# 5x_SFH_Hoeller_ES.net
KiCad netlist of a schematic drawn in EAGLE
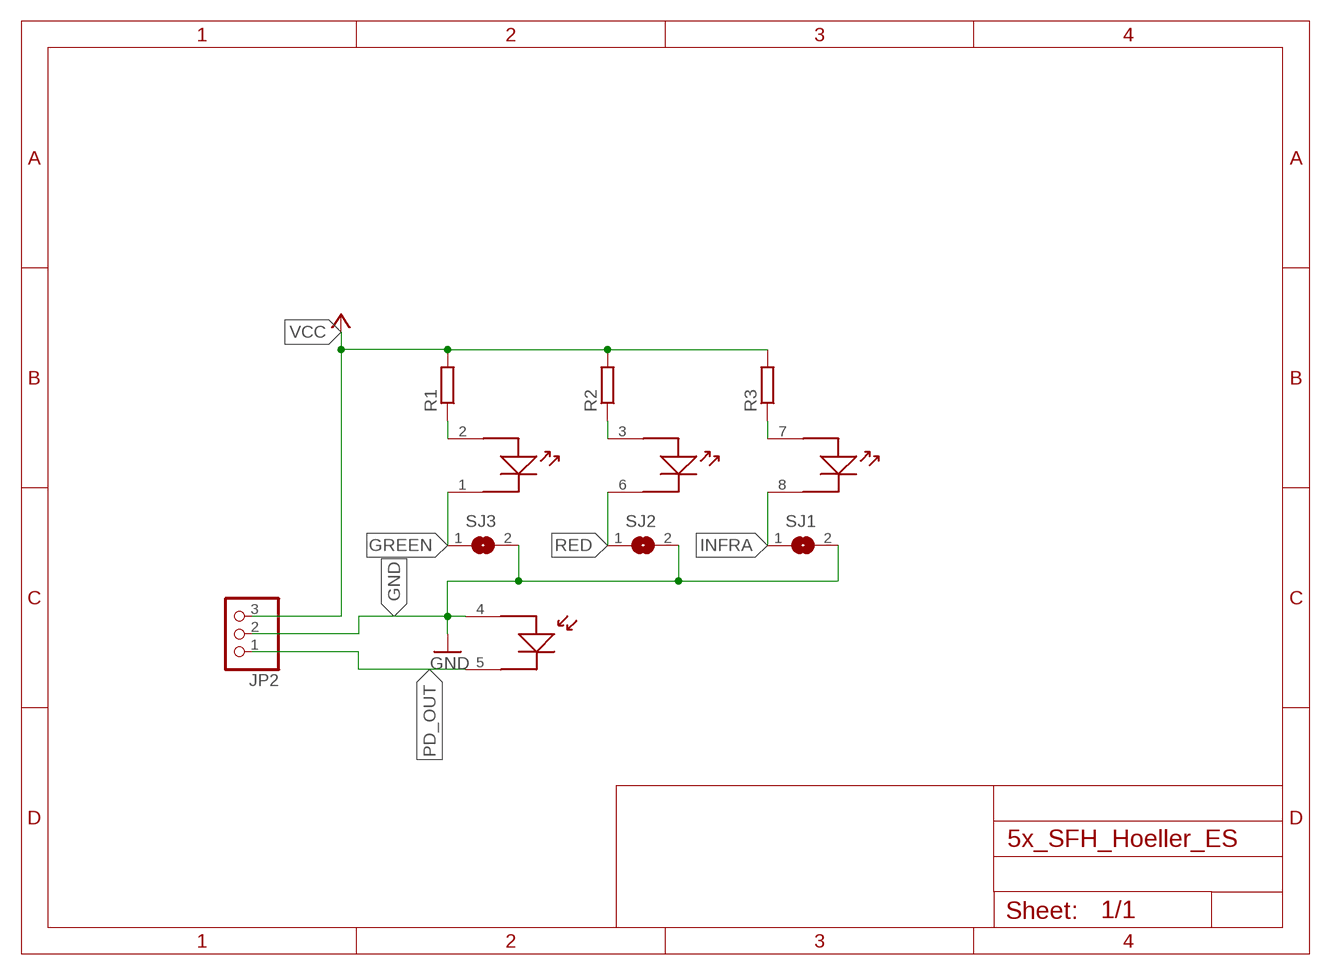
[diagram p0: schematic, sheet 1]

(export (version "E")
  (design (tool "Eeschema 10.0.6"))
  (components
    (comp (ref "JP2")
      (value "PINHD-1X3")
      (footprint "eagle-import:1X03")
      (libsource (lib "eagle-import") (part "PINHD-1X3"))
    )
    (comp (ref "PD-")
      (value "SFH7050_SFH7050")
      (footprint "eagle-import:SFH7050_SFH7050")
      (libsource (lib "eagle-import") (part "SFH7050_SFH7050"))
    )
    (comp (ref "R1")
      (value "R-EU_R0603")
      (footprint "eagle-import:R0603")
      (libsource (lib "eagle-import") (part "R-EU_R0603"))
    )
    (comp (ref "R2")
      (value "R-EU_R0603")
      (footprint "eagle-import:R0603")
      (libsource (lib "eagle-import") (part "R-EU_R0603"))
    )
    (comp (ref "R3")
      (value "R-EU_R0603")
      (footprint "eagle-import:R0603")
      (libsource (lib "eagle-import") (part "R-EU_R0603"))
    )
    (comp (ref "SJ1") (value "SJ") (footprint "eagle-import:SJ") (libsource (lib "eagle-import") (part "SJ")))
    (comp (ref "SJ2") (value "SJ") (footprint "eagle-import:SJ") (libsource (lib "eagle-import") (part "SJ")))
    (comp (ref "SJ3") (value "SJ") (footprint "eagle-import:SJ") (libsource (lib "eagle-import") (part "SJ")))
  )
  (nets
    (net (code "1") (name "GND") (class "Default")
      (node (ref "JP2") (pin "2") (pinfunction "2_2") (pintype "passive"))
      (node (ref "PD-") (pin "4") (pinfunction "A_4") (pintype "bidirectional"))
      (node (ref "SJ1") (pin "2") (pinfunction "2_2") (pintype "passive"))
      (node (ref "SJ2") (pin "2") (pinfunction "2_2") (pintype "passive"))
      (node (ref "SJ3") (pin "2") (pinfunction "2_2") (pintype "passive"))
    )
    (net (code "2") (name "GREEN") (class "Default")
      (node (ref "PD-") (pin "1") (pinfunction "C_1") (pintype "bidirectional"))
      (node (ref "SJ3") (pin "1") (pinfunction "1_1") (pintype "passive"))
    )
    (net (code "3") (name "INFRA") (class "Default")
      (node (ref "PD-") (pin "8") (pinfunction "C_8") (pintype "bidirectional"))
      (node (ref "SJ1") (pin "1") (pinfunction "1_1") (pintype "passive"))
    )
    (net (code "4") (name "Net-(PD-A-A)") (class "Default")
      (node (ref "PD-") (pin "2") (pinfunction "A_2") (pintype "bidirectional"))
      (node (ref "R1") (pin "1") (pinfunction "1_1") (pintype "passive"))
    )
    (net (code "5") (name "Net-(PD-B-A)") (class "Default")
      (node (ref "PD-") (pin "3") (pinfunction "A_3") (pintype "bidirectional"))
      (node (ref "R2") (pin "1") (pinfunction "1_1") (pintype "passive"))
    )
    (net (code "6") (name "Net-(PD-C-A)") (class "Default")
      (node (ref "PD-") (pin "7") (pinfunction "A_7") (pintype "bidirectional"))
      (node (ref "R3") (pin "1") (pinfunction "1_1") (pintype "passive"))
    )
    (net (code "7") (name "PD_OUT") (class "Default")
      (node (ref "JP2") (pin "1") (pinfunction "1_1") (pintype "passive"))
      (node (ref "PD-") (pin "5") (pinfunction "C_5") (pintype "bidirectional"))
    )
    (net (code "8") (name "RED") (class "Default")
      (node (ref "PD-") (pin "6") (pinfunction "C_6") (pintype "bidirectional"))
      (node (ref "SJ2") (pin "1") (pinfunction "1_1") (pintype "passive"))
    )
    (net (code "9") (name "VCC") (class "Default")
      (node (ref "JP2") (pin "3") (pinfunction "3_3") (pintype "passive"))
      (node (ref "R1") (pin "2") (pinfunction "2_2") (pintype "passive"))
      (node (ref "R2") (pin "2") (pinfunction "2_2") (pintype "passive"))
      (node (ref "R3") (pin "2") (pinfunction "2_2") (pintype "passive"))
    )
  )
)
